# pulse_mux_SchDoc_bak.net
KiCad netlist of a schematic drawn in Altium Designer
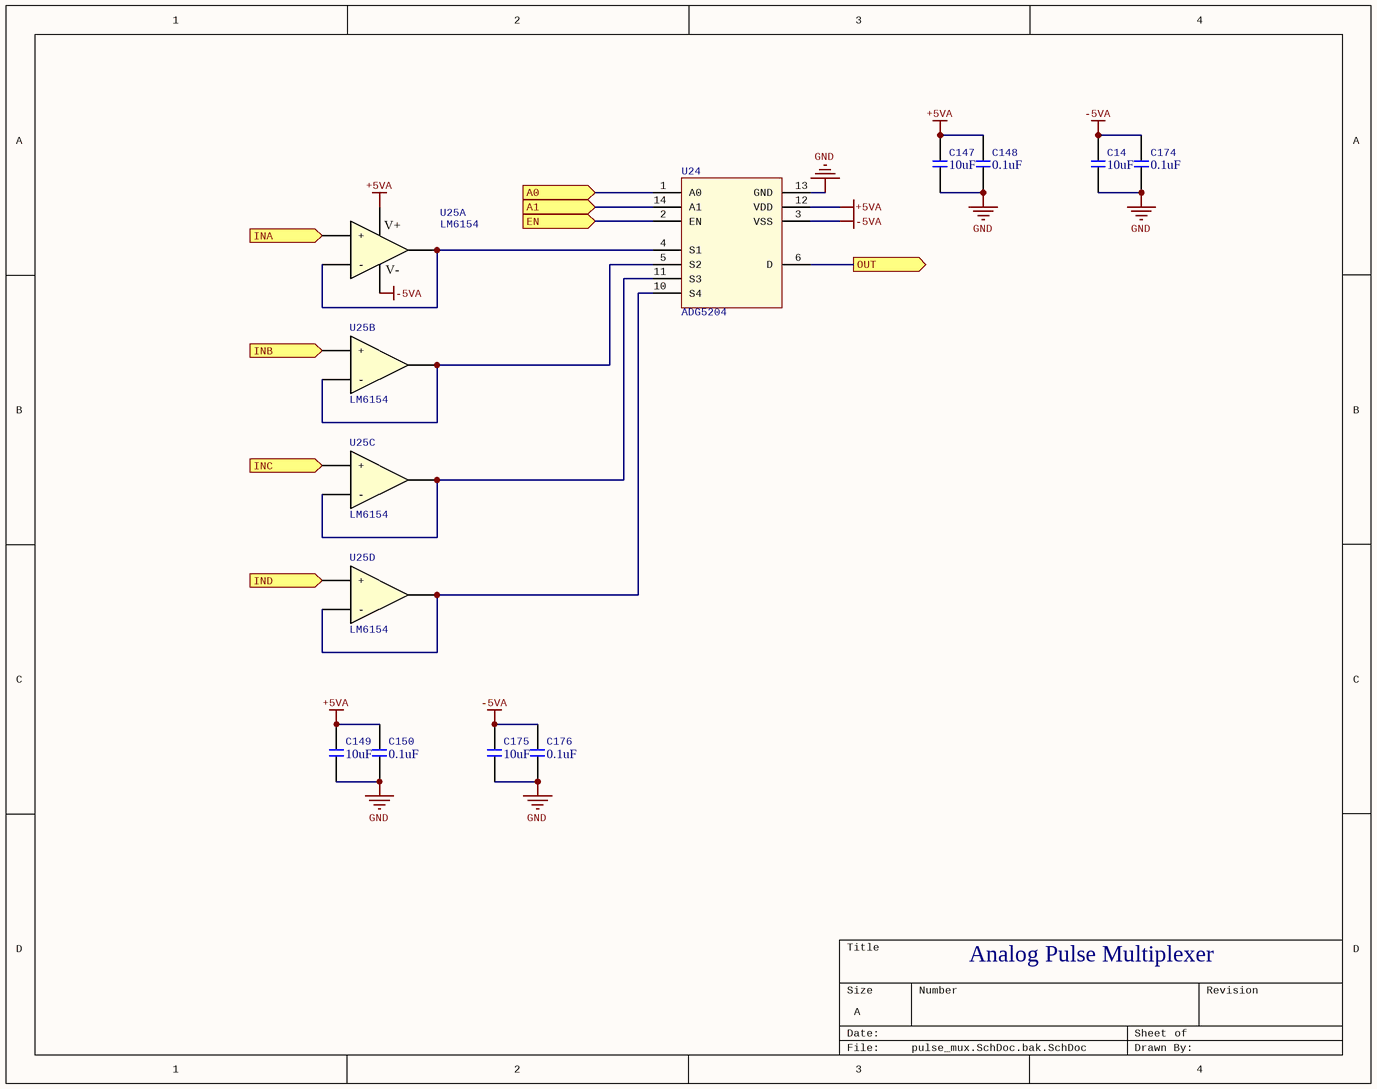
[diagram p0: pulse_mux.SchDoc.bak.SchDoc]

(export (version "E")
  (design (tool "Eeschema 10.0.6"))
  (components
    (comp (ref "C14") (value "10uF") (footprint "C0603") (libsource (lib "tester_board") (part "C10uF")))
    (comp (ref "C147") (value "10uF") (footprint "C0603") (libsource (lib "tester_board") (part "C10uF")))
    (comp (ref "C148")
      (value "0.1uF")
      (footprint "C0402")
      (description "0.1 uF SMD Capacitor")
      (libsource (lib "tester_board") (part "C0.1uF"))
    )
    (comp (ref "C149") (value "10uF") (footprint "C0603") (libsource (lib "tester_board") (part "C10uF")))
    (comp (ref "C150")
      (value "0.1uF")
      (footprint "C0402")
      (description "0.1 uF SMD Capacitor")
      (libsource (lib "tester_board") (part "C0.1uF"))
    )
    (comp (ref "C174")
      (value "0.1uF")
      (footprint "C0402")
      (description "0.1 uF SMD Capacitor")
      (libsource (lib "tester_board") (part "C0.1uF"))
    )
    (comp (ref "C175") (value "10uF") (footprint "C0603") (libsource (lib "tester_board") (part "C10uF")))
    (comp (ref "C176")
      (value "0.1uF")
      (footprint "C0402")
      (description "0.1 uF SMD Capacitor")
      (libsource (lib "tester_board") (part "C0.1uF"))
    )
    (comp (ref "U24")
      (value "ADG5204")
      (footprint "TSSOP-14")
      (description "4 Input Analog Multiplexer")
      (libsource (lib "tester_board") (part "ADG5204"))
    )
    (comp (ref "U25") (value "LM6154") (footprint "SOIC-14") (libsource (lib "tester_board") (part "LM6154")))
  )
  (nets
    (net (code "1") (name "+5VA") (class "Default")
      (node (ref "C147") (pin "2") (pinfunction "2_2") (pintype "passive"))
      (node (ref "C148") (pin "2") (pinfunction "2_2") (pintype "passive"))
      (node (ref "C149") (pin "2") (pinfunction "2_2") (pintype "passive"))
      (node (ref "C150") (pin "2") (pinfunction "2_2") (pintype "passive"))
      (node (ref "U24") (pin "12") (pinfunction "VDD_12") (pintype "passive"))
      (node (ref "U25") (pin "4") (pinfunction "V+_4") (pintype "passive"))
    )
    (net (code "2") (name "-5VA") (class "Default")
      (node (ref "C14") (pin "2") (pinfunction "2_2") (pintype "passive"))
      (node (ref "C174") (pin "2") (pinfunction "2_2") (pintype "passive"))
      (node (ref "C175") (pin "2") (pinfunction "2_2") (pintype "passive"))
      (node (ref "C176") (pin "2") (pinfunction "2_2") (pintype "passive"))
      (node (ref "U24") (pin "3") (pinfunction "VSS_3") (pintype "passive"))
      (node (ref "U25") (pin "11") (pinfunction "V-_11") (pintype "passive"))
    )
    (net (code "3") (name "/A0") (class "Default")
      (node (ref "U24") (pin "1") (pinfunction "A0_1") (pintype "passive"))
    )
    (net (code "4") (name "/A1") (class "Default")
      (node (ref "U24") (pin "14") (pinfunction "A1_14") (pintype "passive"))
    )
    (net (code "5") (name "/EN") (class "Default")
      (node (ref "U24") (pin "2") (pinfunction "EN_2") (pintype "passive"))
    )
    (net (code "6") (name "/INA") (class "Default")
      (node (ref "U25") (pin "3") (pinfunction "+_3") (pintype "passive"))
    )
    (net (code "7") (name "/INB") (class "Default")
      (node (ref "U25") (pin "5") (pinfunction "+_5") (pintype "passive"))
    )
    (net (code "8") (name "/INC") (class "Default")
      (node (ref "U25") (pin "10") (pinfunction "+_10") (pintype "passive"))
    )
    (net (code "9") (name "/IND") (class "Default")
      (node (ref "U25") (pin "12") (pinfunction "+_12") (pintype "passive"))
    )
    (net (code "10") (name "/OUT") (class "Default")
      (node (ref "U24") (pin "6") (pinfunction "D_6") (pintype "passive"))
    )
    (net (code "11") (name "GND") (class "Default")
      (node (ref "C14") (pin "1") (pinfunction "5_1") (pintype "passive"))
      (node (ref "C147") (pin "1") (pinfunction "5_1") (pintype "passive"))
      (node (ref "C148") (pin "1") (pinfunction "5_1") (pintype "passive"))
      (node (ref "C149") (pin "1") (pinfunction "5_1") (pintype "passive"))
      (node (ref "C150") (pin "1") (pinfunction "5_1") (pintype "passive"))
      (node (ref "C174") (pin "1") (pinfunction "5_1") (pintype "passive"))
      (node (ref "C175") (pin "1") (pinfunction "5_1") (pintype "passive"))
      (node (ref "C176") (pin "1") (pinfunction "5_1") (pintype "passive"))
      (node (ref "U24") (pin "13") (pinfunction "GND_13") (pintype "passive"))
    )
    (net (code "12") (name "Net-(U24-S1)") (class "Default")
      (node (ref "U24") (pin "4") (pinfunction "S1_4") (pintype "passive"))
      (node (ref "U25") (pin "1") (pinfunction "OUT_1") (pintype "passive"))
      (node (ref "U25") (pin "2") (pinfunction "-_2") (pintype "passive"))
    )
    (net (code "13") (name "Net-(U24-S2)") (class "Default")
      (node (ref "U24") (pin "5") (pinfunction "S2_5") (pintype "passive"))
      (node (ref "U25") (pin "6") (pinfunction "-_6") (pintype "passive"))
      (node (ref "U25") (pin "7") (pinfunction "OUT_7") (pintype "passive"))
    )
    (net (code "14") (name "Net-(U24-S3)") (class "Default")
      (node (ref "U24") (pin "11") (pinfunction "S3_11") (pintype "passive"))
      (node (ref "U25") (pin "8") (pinfunction "OUT_8") (pintype "passive"))
      (node (ref "U25") (pin "9") (pinfunction "-_9") (pintype "passive"))
    )
    (net (code "15") (name "Net-(U24-S4)") (class "Default")
      (node (ref "U24") (pin "10") (pinfunction "S4_10") (pintype "passive"))
      (node (ref "U25") (pin "13") (pinfunction "-_13") (pintype "passive"))
      (node (ref "U25") (pin "14") (pinfunction "OUT_14") (pintype "passive"))
    )
    (net (code "16") (name "unconnected-(U24-NC-Pad7)") (class "Default")
      (node (ref "U24") (pin "7") (pinfunction "NC_7") (pintype "passive"))
    )
    (net (code "17") (name "unconnected-(U24-NC-Pad8)") (class "Default")
      (node (ref "U24") (pin "8") (pinfunction "NC_8") (pintype "passive"))
    )
    (net (code "18") (name "unconnected-(U24-NC-Pad9)") (class "Default")
      (node (ref "U24") (pin "9") (pinfunction "NC_9") (pintype "passive"))
    )
  )
)
